# Sheet4.net
KiCad netlist of a schematic drawn in Altium Designer
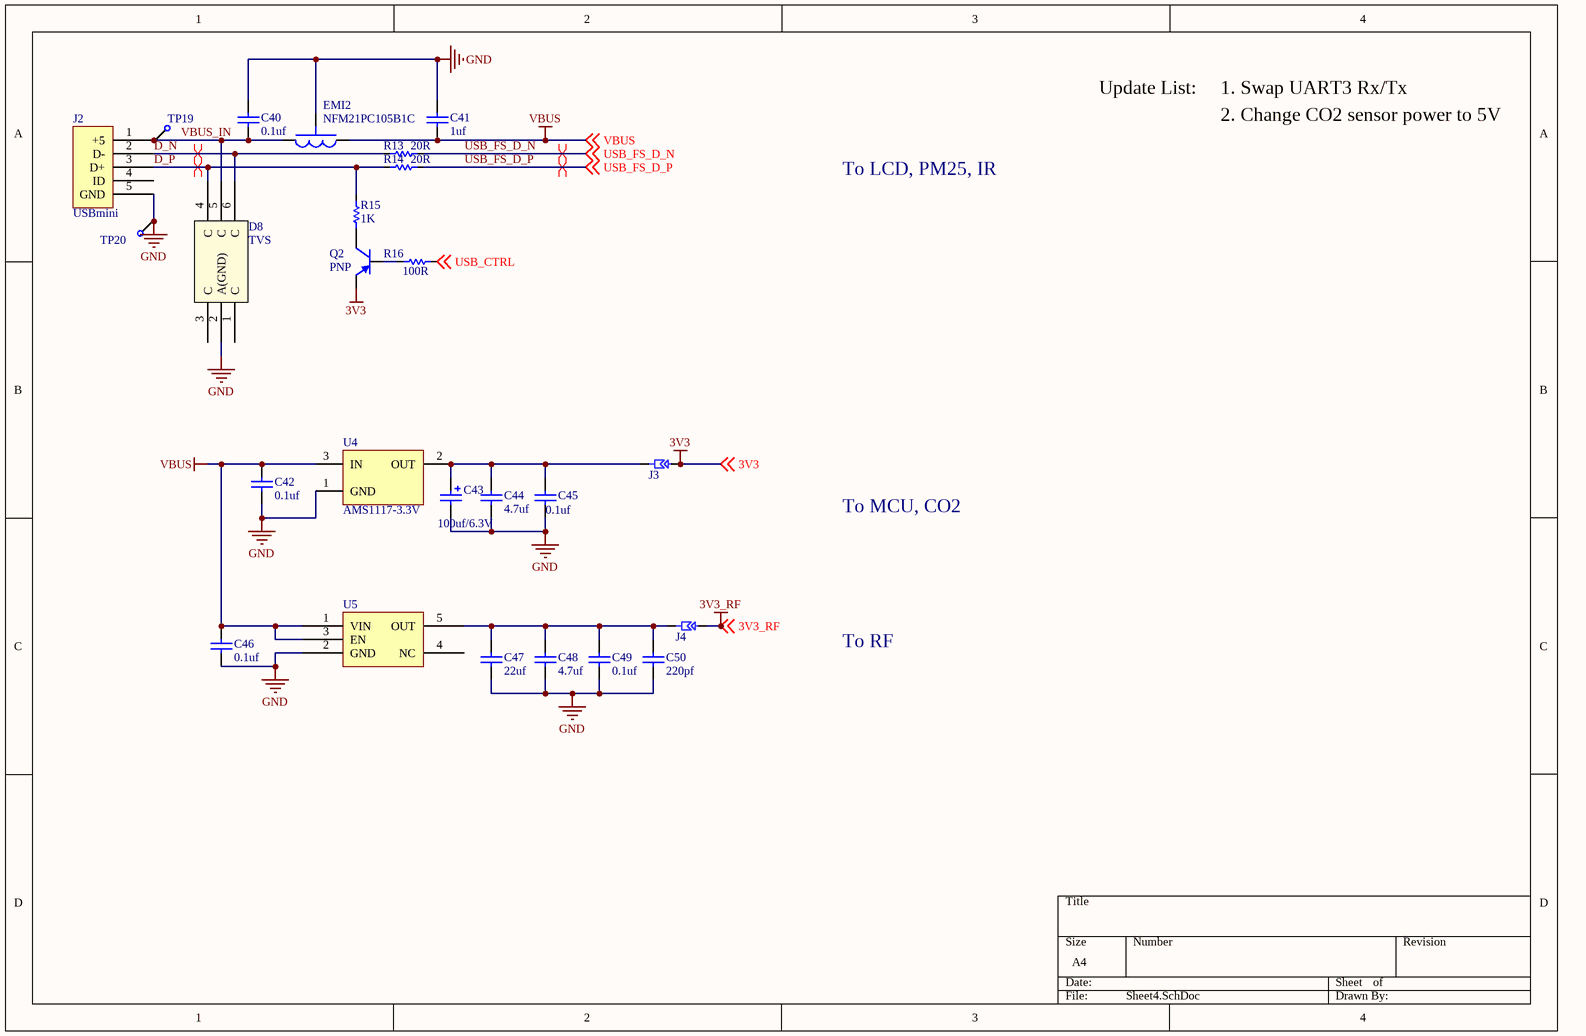
[diagram p0: Sheet4.SchDoc]

(export (version "E")
  (design (tool "Eeschema 10.0.6"))
  (components
    (comp (ref "C40")
      (value "0.1uf")
      (footprint "C0603")
      (description "Capacitor")
      (libsource (lib "liber") (part "Cap"))
    )
    (comp (ref "C41")
      (value "1uf")
      (footprint "C0603")
      (description "Capacitor")
      (libsource (lib "liber") (part "Cap"))
    )
    (comp (ref "C42")
      (value "0.1uf")
      (footprint "C0603")
      (description "Capacitor")
      (libsource (lib "liber") (part "Cap"))
    )
    (comp (ref "C43")
      (value "100uf/6.3V")
      (footprint "C_B型")
      (description "Polarized Capacitor (Radial)")
      (fields (field (name "VOLTAGE") "25V"))
      (libsource (lib "liber") (part "Cap+"))
    )
    (comp (ref "C44")
      (value "4.7uf")
      (footprint "C0805")
      (description "Capacitor")
      (libsource (lib "liber") (part "Cap"))
    )
    (comp (ref "C45")
      (value "0.1uf")
      (footprint "C0603")
      (description "Capacitor")
      (libsource (lib "liber") (part "Cap"))
    )
    (comp (ref "C46")
      (value "0.1uf")
      (footprint "C0603")
      (description "Capacitor")
      (libsource (lib "liber") (part "Cap"))
    )
    (comp (ref "C47")
      (value "22uf")
      (footprint "C1206")
      (description "Capacitor")
      (libsource (lib "liber") (part "Cap"))
    )
    (comp (ref "C48")
      (value "4.7uf")
      (footprint "C0603")
      (description "Capacitor")
      (libsource (lib "liber") (part "Cap"))
    )
    (comp (ref "C49")
      (value "0.1uf")
      (footprint "C0603")
      (description "Capacitor")
      (libsource (lib "liber") (part "Cap"))
    )
    (comp (ref "C50")
      (value "220pf")
      (footprint "C0603")
      (description "Capacitor")
      (libsource (lib "liber") (part "Cap"))
    )
    (comp (ref "D8") (value "TVS") (footprint "USBLC6-2") (libsource (lib "liber") (part "USBLC6-2")))
    (comp (ref "EMI2")
      (value "NFM21PC105B1C")
      (footprint "NFM21PC")
      (libsource (lib "liber") (part "NFM21PC105B1C"))
    )
    (comp (ref "J2") (value "USBmini") (footprint "USB_MICRO_B") (libsource (lib "liber") (part "USB_mini")))
    (comp (ref "J3") (value "JUMPER") (footprint "liber:Jsmall") (libsource (lib "liber") (part "J")))
    (comp (ref "J4") (value "JUMPER") (footprint "liber:Jsmall") (libsource (lib "liber") (part "J")))
    (comp (ref "Q2")
      (value "PNP")
      (footprint "SOT23_BJT")
      (description "PNP Bipolar Transistor")
      (fields (field (name "PUBLISHER") "Altium Limited"))
      (libsource (lib "liber") (part "PNP"))
    )
    (comp (ref "R13")
      (value "20R")
      (footprint "R0603")
      (fields (field (name "PUBLISHER") "Altium Limited"))
      (libsource (lib "liber") (part "Res"))
    )
    (comp (ref "R14")
      (value "20R")
      (footprint "R0603")
      (fields (field (name "PUBLISHER") "Altium Limited"))
      (libsource (lib "liber") (part "Res"))
    )
    (comp (ref "R15")
      (value "1K")
      (footprint "R0603")
      (fields (field (name "PUBLISHER") "Altium Limited"))
      (libsource (lib "liber") (part "Res"))
    )
    (comp (ref "R16")
      (value "100R")
      (footprint "R0603")
      (fields (field (name "PUBLISHER") "Altium Limited"))
      (libsource (lib "liber") (part "Res"))
    )
    (comp (ref "TP19")
      (value "TestPoint")
      (footprint "TP_0.8")
      (description "一个测试点")
      (libsource (lib "liber") (part "TestPoint"))
    )
    (comp (ref "TP20")
      (value "TestPoint")
      (footprint "TP_0.8")
      (description "一个测试点")
      (libsource (lib "liber") (part "TestPoint"))
    )
    (comp (ref "U4") (value "AMS1117-3.3V") (footprint "SOT223") (libsource (lib "liber") (part "1117")))
    (comp (ref "U5") (value "ADP151") (footprint "liber:ADP151") (libsource (lib "liber") (part "ADP151")))
  )
  (nets
    (net (code "1") (name "/D_N") (class "Default")
      (node (ref "D8") (pin "6") (pinfunction "C_6") (pintype "passive"))
      (node (ref "J2") (pin "2") (pinfunction "D-_2") (pintype "passive"))
      (node (ref "R13") (pin "1") (pinfunction "1_1") (pintype "passive"))
    )
    (net (code "2") (name "/D_P") (class "Default")
      (node (ref "D8") (pin "4") (pinfunction "C_4") (pintype "passive"))
      (node (ref "J2") (pin "3") (pinfunction "D+_3") (pintype "passive"))
      (node (ref "R14") (pin "1") (pinfunction "1_1") (pintype "passive"))
      (node (ref "R15") (pin "2") (pinfunction "2_2") (pintype "passive"))
    )
    (net (code "3") (name "/VBUS_IN") (class "Default")
      (node (ref "C40") (pin "1") (pinfunction "1_1") (pintype "passive"))
      (node (ref "D8") (pin "5") (pinfunction "C_5") (pintype "passive"))
      (node (ref "EMI2") (pin "3") (pinfunction "3_3") (pintype "passive"))
      (node (ref "J2") (pin "1") (pinfunction "+5_1") (pintype "passive"))
      (node (ref "TP19") (pin "1") (pinfunction "1_1") (pintype "passive"))
    )
    (net (code "4") (name "3V3") (class "Default")
      (node (ref "J3") (pin "2") (pinfunction "2_2") (pintype "passive"))
      (node (ref "Q2") (pin "1") (pinfunction "E_1") (pintype "passive"))
    )
    (net (code "5") (name "3V3_RF") (class "Default")
      (node (ref "J4") (pin "2") (pinfunction "2_2") (pintype "passive"))
    )
    (net (code "6") (name "GND") (class "Default")
      (node (ref "C40") (pin "2") (pinfunction "2_2") (pintype "passive"))
      (node (ref "C41") (pin "2") (pinfunction "2_2") (pintype "passive"))
      (node (ref "C42") (pin "1") (pinfunction "1_1") (pintype "passive"))
      (node (ref "C43") (pin "2") (pinfunction "2_2") (pintype "passive"))
      (node (ref "C44") (pin "1") (pinfunction "1_1") (pintype "passive"))
      (node (ref "C45") (pin "1") (pinfunction "1_1") (pintype "passive"))
      (node (ref "C46") (pin "1") (pinfunction "1_1") (pintype "passive"))
      (node (ref "C47") (pin "1") (pinfunction "1_1") (pintype "passive"))
      (node (ref "C48") (pin "1") (pinfunction "1_1") (pintype "passive"))
      (node (ref "C49") (pin "1") (pinfunction "1_1") (pintype "passive"))
      (node (ref "C50") (pin "1") (pinfunction "1_1") (pintype "passive"))
      (node (ref "D8") (pin "2") (pinfunction "A(GND)_2") (pintype "passive"))
      (node (ref "EMI2") (pin "2") (pinfunction "2_2") (pintype "passive"))
      (node (ref "J2") (pin "5") (pinfunction "GND_5") (pintype "passive"))
      (node (ref "TP20") (pin "1") (pinfunction "1_1") (pintype "passive"))
      (node (ref "U4") (pin "1") (pinfunction "GND_1") (pintype "passive"))
      (node (ref "U5") (pin "2") (pinfunction "GND_2") (pintype "passive"))
    )
    (net (code "7") (name "Net-(Q2-B)") (class "Default")
      (node (ref "Q2") (pin "2") (pinfunction "B_2") (pintype "passive"))
      (node (ref "R16") (pin "1") (pinfunction "1_1") (pintype "passive"))
    )
    (net (code "8") (name "Net-(Q2-C)") (class "Default")
      (node (ref "Q2") (pin "3") (pinfunction "C_3") (pintype "passive"))
      (node (ref "R15") (pin "1") (pinfunction "1_1") (pintype "passive"))
    )
    (net (code "9") (name "Net-(U4-OUT)") (class "Default")
      (node (ref "C43") (pin "1") (pinfunction "1_1") (pintype "passive"))
      (node (ref "C44") (pin "2") (pinfunction "2_2") (pintype "passive"))
      (node (ref "C45") (pin "2") (pinfunction "2_2") (pintype "passive"))
      (node (ref "J3") (pin "1") (pinfunction "1_1") (pintype "passive"))
      (node (ref "U4") (pin "2") (pinfunction "OUT_2") (pintype "passive"))
    )
    (net (code "10") (name "Net-(U5-OUT)") (class "Default")
      (node (ref "C47") (pin "2") (pinfunction "2_2") (pintype "passive"))
      (node (ref "C48") (pin "2") (pinfunction "2_2") (pintype "passive"))
      (node (ref "C49") (pin "2") (pinfunction "2_2") (pintype "passive"))
      (node (ref "C50") (pin "2") (pinfunction "2_2") (pintype "passive"))
      (node (ref "J4") (pin "1") (pinfunction "1_1") (pintype "passive"))
      (node (ref "U5") (pin "5") (pinfunction "OUT_5") (pintype "passive"))
    )
    (net (code "11") (name "USB_CTRL") (class "Default")
      (node (ref "R16") (pin "2") (pinfunction "2_2") (pintype "passive"))
    )
    (net (code "12") (name "USB_FS_D_N") (class "Default")
      (node (ref "R13") (pin "2") (pinfunction "2_2") (pintype "passive"))
    )
    (net (code "13") (name "USB_FS_D_P") (class "Default")
      (node (ref "R14") (pin "2") (pinfunction "2_2") (pintype "passive"))
    )
    (net (code "14") (name "VBUS") (class "Default")
      (node (ref "C41") (pin "1") (pinfunction "1_1") (pintype "passive"))
      (node (ref "C42") (pin "2") (pinfunction "2_2") (pintype "passive"))
      (node (ref "C46") (pin "2") (pinfunction "2_2") (pintype "passive"))
      (node (ref "EMI2") (pin "1") (pinfunction "1_1") (pintype "passive"))
      (node (ref "U4") (pin "3") (pinfunction "IN_3") (pintype "passive"))
      (node (ref "U5") (pin "1") (pinfunction "VIN_1") (pintype "passive"))
      (node (ref "U5") (pin "3") (pinfunction "EN_3") (pintype "passive"))
    )
    (net (code "15") (name "unconnected-(D8-C-Pad1)") (class "Default")
      (node (ref "D8") (pin "1") (pinfunction "C_1") (pintype "passive"))
    )
    (net (code "16") (name "unconnected-(D8-C-Pad3)") (class "Default")
      (node (ref "D8") (pin "3") (pinfunction "C_3") (pintype "passive"))
    )
    (net (code "17") (name "unconnected-(J2-ID-Pad4)") (class "Default")
      (node (ref "J2") (pin "4") (pinfunction "ID_4") (pintype "passive"))
    )
    (net (code "18") (name "unconnected-(U5-NC-Pad4)") (class "Default")
      (node (ref "U5") (pin "4") (pinfunction "NC_4") (pintype "passive"))
    )
  )
)
